# bitraf-rpi-breakout.net
KiCad netlist of a schematic drawn in EAGLE
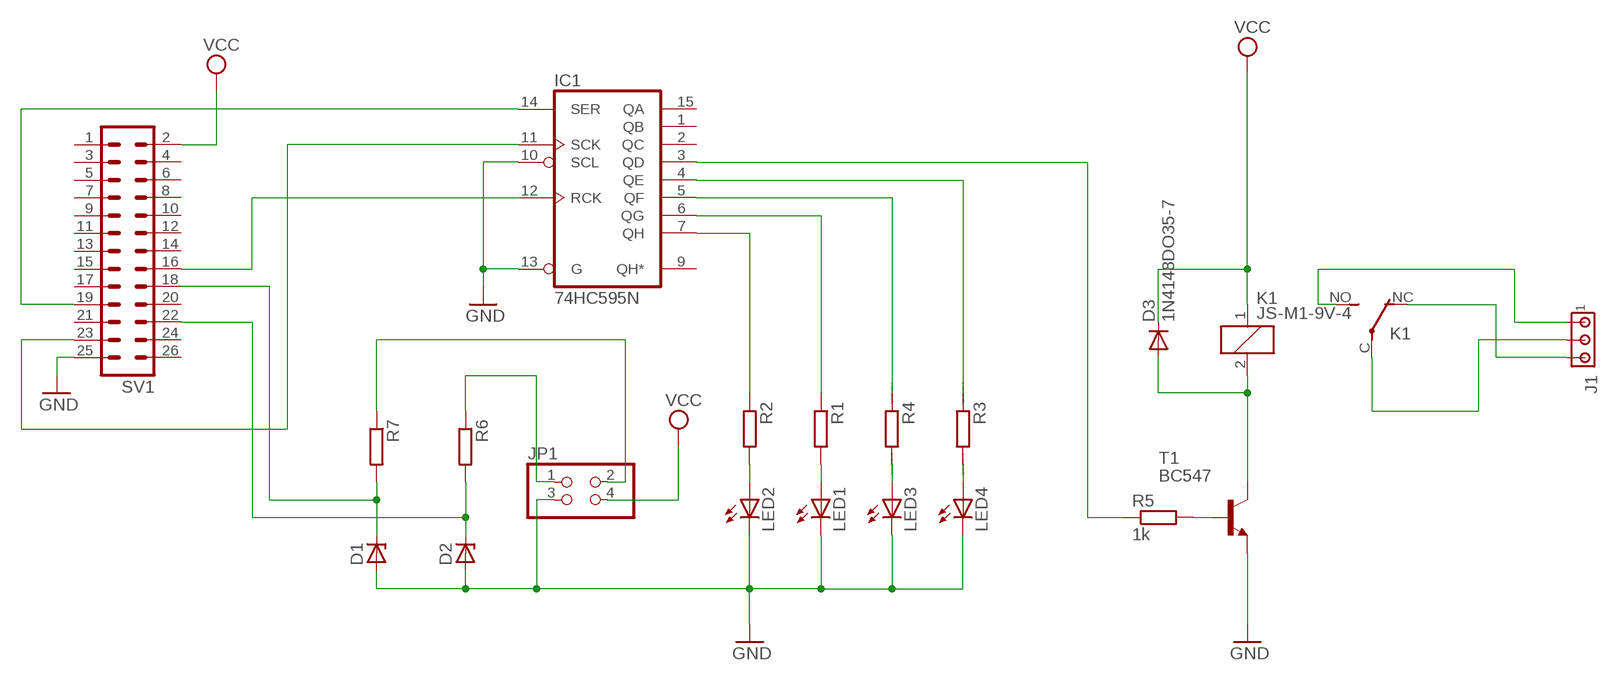
[diagram p0: schematic, sheet 1]

(export (version "E")
  (design (tool "Eeschema 10.0.6"))
  (components
    (comp (ref "D1")
      (value "ZENER-DIODEZD-7.5")
      (footprint "eagle-import:ZDIO-7.5")
      (libsource (lib "eagle-import") (part "ZENER-DIODEZD-7.5"))
    )
    (comp (ref "D2")
      (value "ZENER-DIODEZD-7.5")
      (footprint "eagle-import:ZDIO-7.5")
      (libsource (lib "eagle-import") (part "ZENER-DIODEZD-7.5"))
    )
    (comp (ref "D3")
      (value "1N4148DO35-7")
      (footprint "eagle-import:DO35-7")
      (libsource (lib "eagle-import") (part "1N4148DO35-7"))
    )
    (comp (ref "IC1")
      (value "74HC595N")
      (footprint "eagle-import:DIL16")
      (libsource (lib "eagle-import") (part "74595NHC"))
    )
    (comp (ref "J1")
      (value "MTA03-156")
      (footprint "eagle-import:1X3MTA")
      (libsource (lib "eagle-import") (part "MTA03-156"))
    )
    (comp (ref "JP1")
      (value "PINHD-2X2")
      (footprint "eagle-import:2X02")
      (libsource (lib "eagle-import") (part "PINHD-2X2"))
    )
    (comp (ref "K1")
      (value "JS-M1-9V-4")
      (footprint "eagle-import:JS-M")
      (libsource (lib "eagle-import") (part "JS-M1-9V-4"))
    )
    (comp (ref "LED1")
      (value "LED3MM")
      (footprint "eagle-import:LED3MM")
      (libsource (lib "eagle-import") (part "LED3MM"))
    )
    (comp (ref "LED2")
      (value "LED3MM")
      (footprint "eagle-import:LED3MM")
      (libsource (lib "eagle-import") (part "LED3MM"))
    )
    (comp (ref "LED3")
      (value "LEDSML1206")
      (footprint "eagle-import:SML1206")
      (libsource (lib "eagle-import") (part "LEDSML1206"))
    )
    (comp (ref "LED4")
      (value "LEDSML1206")
      (footprint "eagle-import:SML1206")
      (libsource (lib "eagle-import") (part "LEDSML1206"))
    )
    (comp (ref "R1")
      (value "R-EU_0204/7")
      (footprint "eagle-import:0204_7")
      (libsource (lib "eagle-import") (part "R-EU_0204/7"))
    )
    (comp (ref "R2")
      (value "R-EU_0204/7")
      (footprint "eagle-import:0204_7")
      (libsource (lib "eagle-import") (part "R-EU_0204/7"))
    )
    (comp (ref "R3")
      (value "RR1206")
      (footprint "eagle-import:R1206")
      (libsource (lib "eagle-import") (part "RR1206"))
    )
    (comp (ref "R4")
      (value "RR1206")
      (footprint "eagle-import:R1206")
      (libsource (lib "eagle-import") (part "RR1206"))
    )
    (comp (ref "R5")
      (value "1k")
      (footprint "eagle-import:0204_7")
      (libsource (lib "eagle-import") (part "R-EU_0204/7"))
    )
    (comp (ref "R6")
      (value "R-EU_0204/7")
      (footprint "eagle-import:0204_7")
      (libsource (lib "eagle-import") (part "R-EU_0204/7"))
    )
    (comp (ref "R7")
      (value "R-EU_0204/7")
      (footprint "eagle-import:0204_7")
      (libsource (lib "eagle-import") (part "R-EU_0204/7"))
    )
    (comp (ref "SV1")
      (value "ML26")
      (footprint "eagle-import:ML26")
      (libsource (lib "eagle-import") (part "ML26"))
    )
    (comp (ref "T1")
      (value "BC547")
      (footprint "eagle-import:TO92")
      (libsource (lib "eagle-import") (part "BC547"))
    )
  )
  (nets
    (net (code "1") (name "GND") (class "Default")
      (node (ref "D1") (pin "A") (pinfunction "A_A") (pintype "passive"))
      (node (ref "D2") (pin "A") (pinfunction "A_A") (pintype "passive"))
      (node (ref "IC1") (pin "10") (pinfunction "SCL_10") (pintype "input"))
      (node (ref "IC1") (pin "13") (pinfunction "G_13") (pintype "input"))
      (node (ref "JP1") (pin "3") (pinfunction "3_3") (pintype "passive"))
      (node (ref "LED1") (pin "K") (pinfunction "C_K") (pintype "passive"))
      (node (ref "LED2") (pin "K") (pinfunction "C_K") (pintype "passive"))
      (node (ref "LED3") (pin "C") (pinfunction "C_C") (pintype "passive"))
      (node (ref "LED4") (pin "C") (pinfunction "C_C") (pintype "passive"))
      (node (ref "SV1") (pin "25") (pinfunction "25_25") (pintype "passive"))
      (node (ref "T1") (pin "1") (pinfunction "E_1") (pintype "passive"))
    )
    (net (code "2") (name "Net-(D1-PadC)") (class "Default")
      (node (ref "D1") (pin "C") (pinfunction "C_C") (pintype "passive"))
      (node (ref "R7") (pin "2") (pinfunction "2_2") (pintype "passive"))
      (node (ref "SV1") (pin "18") (pinfunction "18_18") (pintype "passive"))
    )
    (net (code "3") (name "Net-(D2-PadC)") (class "Default")
      (node (ref "D2") (pin "C") (pinfunction "C_C") (pintype "passive"))
      (node (ref "R6") (pin "2") (pinfunction "2_2") (pintype "passive"))
      (node (ref "SV1") (pin "22") (pinfunction "22_22") (pintype "passive"))
    )
    (net (code "4") (name "Net-(IC1A-QD)") (class "Default")
      (node (ref "IC1") (pin "3") (pinfunction "QD_3") (pintype "tri_state"))
      (node (ref "R5") (pin "1") (pinfunction "1_1") (pintype "passive"))
    )
    (net (code "5") (name "Net-(IC1A-QE)") (class "Default")
      (node (ref "IC1") (pin "4") (pinfunction "QE_4") (pintype "tri_state"))
      (node (ref "R3") (pin "1") (pinfunction "1_1") (pintype "passive"))
    )
    (net (code "6") (name "Net-(IC1A-QF)") (class "Default")
      (node (ref "IC1") (pin "5") (pinfunction "QF_5") (pintype "tri_state"))
      (node (ref "R4") (pin "1") (pinfunction "1_1") (pintype "passive"))
    )
    (net (code "7") (name "Net-(IC1A-QG)") (class "Default")
      (node (ref "IC1") (pin "6") (pinfunction "QG_6") (pintype "tri_state"))
      (node (ref "R1") (pin "1") (pinfunction "1_1") (pintype "passive"))
    )
    (net (code "8") (name "Net-(IC1A-QH)") (class "Default")
      (node (ref "IC1") (pin "7") (pinfunction "QH_7") (pintype "tri_state"))
      (node (ref "R2") (pin "1") (pinfunction "1_1") (pintype "passive"))
    )
    (net (code "9") (name "Net-(IC1A-RCK)") (class "Default")
      (node (ref "IC1") (pin "12") (pinfunction "RCK_12") (pintype "input"))
      (node (ref "SV1") (pin "16") (pinfunction "16_16") (pintype "passive"))
    )
    (net (code "10") (name "Net-(IC1A-SCK)") (class "Default")
      (node (ref "IC1") (pin "11") (pinfunction "SCK_11") (pintype "input"))
      (node (ref "SV1") (pin "23") (pinfunction "23_23") (pintype "passive"))
    )
    (net (code "11") (name "Net-(IC1A-SER)") (class "Default")
      (node (ref "IC1") (pin "14") (pinfunction "SER_14") (pintype "input"))
      (node (ref "SV1") (pin "19") (pinfunction "19_19") (pintype "passive"))
    )
    (net (code "12") (name "Net-(JP1-Pad1)") (class "Default")
      (node (ref "JP1") (pin "1") (pinfunction "1_1") (pintype "passive"))
      (node (ref "R6") (pin "1") (pinfunction "1_1") (pintype "passive"))
    )
    (net (code "13") (name "Net-(JP1-Pad2)") (class "Default")
      (node (ref "JP1") (pin "2") (pinfunction "2_2") (pintype "passive"))
      (node (ref "R7") (pin "1") (pinfunction "1_1") (pintype "passive"))
    )
    (net (code "14") (name "Net-(K1B-O)") (class "Default")
      (node (ref "J1") (pin "3") (pinfunction "3_3") (pintype "passive"))
      (node (ref "K1") (pin "NC") (pinfunction "O_NC") (pintype "passive"))
    )
    (net (code "15") (name "Net-(K1B-P)") (class "Default")
      (node (ref "J1") (pin "2") (pinfunction "2_2") (pintype "passive"))
      (node (ref "K1") (pin "C") (pinfunction "P_C") (pintype "passive"))
    )
    (net (code "16") (name "Net-(K1B-S)") (class "Default")
      (node (ref "J1") (pin "1") (pinfunction "1_1") (pintype "passive"))
      (node (ref "K1") (pin "NO") (pinfunction "S_NO") (pintype "passive"))
    )
    (net (code "17") (name "Net-(LED1-PadA)") (class "Default")
      (node (ref "LED1") (pin "A") (pinfunction "A_A") (pintype "passive"))
      (node (ref "R1") (pin "2") (pinfunction "2_2") (pintype "passive"))
    )
    (net (code "18") (name "Net-(LED2-PadA)") (class "Default")
      (node (ref "LED2") (pin "A") (pinfunction "A_A") (pintype "passive"))
      (node (ref "R2") (pin "2") (pinfunction "2_2") (pintype "passive"))
    )
    (net (code "19") (name "Net-(LED3-PadA)") (class "Default")
      (node (ref "LED3") (pin "A") (pinfunction "A_A") (pintype "passive"))
      (node (ref "R4") (pin "2") (pinfunction "2_2") (pintype "passive"))
    )
    (net (code "20") (name "Net-(LED4-PadA)") (class "Default")
      (node (ref "LED4") (pin "A") (pinfunction "A_A") (pintype "passive"))
      (node (ref "R3") (pin "2") (pinfunction "2_2") (pintype "passive"))
    )
    (net (code "21") (name "Net-(T1-B)") (class "Default")
      (node (ref "R5") (pin "2") (pinfunction "2_2") (pintype "passive"))
      (node (ref "T1") (pin "2") (pinfunction "B_2") (pintype "passive"))
    )
    (net (code "22") (name "Net-(T1-C)") (class "Default")
      (node (ref "D3") (pin "A") (pinfunction "A_A") (pintype "passive"))
      (node (ref "K1") (pin "2") (pinfunction "2_2") (pintype "passive"))
      (node (ref "T1") (pin "3") (pinfunction "C_3") (pintype "passive"))
    )
    (net (code "23") (name "VCC") (class "Default")
      (node (ref "D3") (pin "C") (pinfunction "C_C") (pintype "passive"))
      (node (ref "JP1") (pin "4") (pinfunction "4_4") (pintype "passive"))
      (node (ref "K1") (pin "1") (pinfunction "1_1") (pintype "passive"))
      (node (ref "SV1") (pin "2") (pinfunction "2_2") (pintype "passive"))
    )
    (net (code "24") (name "unconnected-(IC1A-QA-Pad15)") (class "Default")
      (node (ref "IC1") (pin "15") (pinfunction "QA_15") (pintype "tri_state"))
    )
    (net (code "25") (name "unconnected-(IC1A-QB-Pad1)") (class "Default")
      (node (ref "IC1") (pin "1") (pinfunction "QB_1") (pintype "tri_state"))
    )
    (net (code "26") (name "unconnected-(IC1A-QC-Pad2)") (class "Default")
      (node (ref "IC1") (pin "2") (pinfunction "QC_2") (pintype "tri_state"))
    )
    (net (code "27") (name "unconnected-(IC1A-QH*-Pad9)") (class "Default")
      (node (ref "IC1") (pin "9") (pinfunction "QH*_9") (pintype "tri_state"))
    )
    (net (code "28") (name "unconnected-(SV1-Pad1)") (class "Default")
      (node (ref "SV1") (pin "1") (pinfunction "1_1") (pintype "passive"))
    )
    (net (code "29") (name "unconnected-(SV1-Pad3)") (class "Default")
      (node (ref "SV1") (pin "3") (pinfunction "3_3") (pintype "passive"))
    )
    (net (code "30") (name "unconnected-(SV1-Pad4)") (class "Default")
      (node (ref "SV1") (pin "4") (pinfunction "4_4") (pintype "passive"))
    )
    (net (code "31") (name "unconnected-(SV1-Pad5)") (class "Default")
      (node (ref "SV1") (pin "5") (pinfunction "5_5") (pintype "passive"))
    )
    (net (code "32") (name "unconnected-(SV1-Pad6)") (class "Default")
      (node (ref "SV1") (pin "6") (pinfunction "6_6") (pintype "passive"))
    )
    (net (code "33") (name "unconnected-(SV1-Pad7)") (class "Default")
      (node (ref "SV1") (pin "7") (pinfunction "7_7") (pintype "passive"))
    )
    (net (code "34") (name "unconnected-(SV1-Pad8)") (class "Default")
      (node (ref "SV1") (pin "8") (pinfunction "8_8") (pintype "passive"))
    )
    (net (code "35") (name "unconnected-(SV1-Pad9)") (class "Default")
      (node (ref "SV1") (pin "9") (pinfunction "9_9") (pintype "passive"))
    )
    (net (code "36") (name "unconnected-(SV1-Pad10)") (class "Default")
      (node (ref "SV1") (pin "10") (pinfunction "10_10") (pintype "passive"))
    )
    (net (code "37") (name "unconnected-(SV1-Pad11)") (class "Default")
      (node (ref "SV1") (pin "11") (pinfunction "11_11") (pintype "passive"))
    )
    (net (code "38") (name "unconnected-(SV1-Pad12)") (class "Default")
      (node (ref "SV1") (pin "12") (pinfunction "12_12") (pintype "passive"))
    )
    (net (code "39") (name "unconnected-(SV1-Pad13)") (class "Default")
      (node (ref "SV1") (pin "13") (pinfunction "13_13") (pintype "passive"))
    )
    (net (code "40") (name "unconnected-(SV1-Pad14)") (class "Default")
      (node (ref "SV1") (pin "14") (pinfunction "14_14") (pintype "passive"))
    )
    (net (code "41") (name "unconnected-(SV1-Pad15)") (class "Default")
      (node (ref "SV1") (pin "15") (pinfunction "15_15") (pintype "passive"))
    )
    (net (code "42") (name "unconnected-(SV1-Pad17)") (class "Default")
      (node (ref "SV1") (pin "17") (pinfunction "17_17") (pintype "passive"))
    )
    (net (code "43") (name "unconnected-(SV1-Pad20)") (class "Default")
      (node (ref "SV1") (pin "20") (pinfunction "20_20") (pintype "passive"))
    )
    (net (code "44") (name "unconnected-(SV1-Pad21)") (class "Default")
      (node (ref "SV1") (pin "21") (pinfunction "21_21") (pintype "passive"))
    )
    (net (code "45") (name "unconnected-(SV1-Pad24)") (class "Default")
      (node (ref "SV1") (pin "24") (pinfunction "24_24") (pintype "passive"))
    )
    (net (code "46") (name "unconnected-(SV1-Pad26)") (class "Default")
      (node (ref "SV1") (pin "26") (pinfunction "26_26") (pintype "passive"))
    )
  )
)
